# motordriver-v5_0_trinamic-controller.net
KiCad netlist of a schematic drawn in Altium Designer
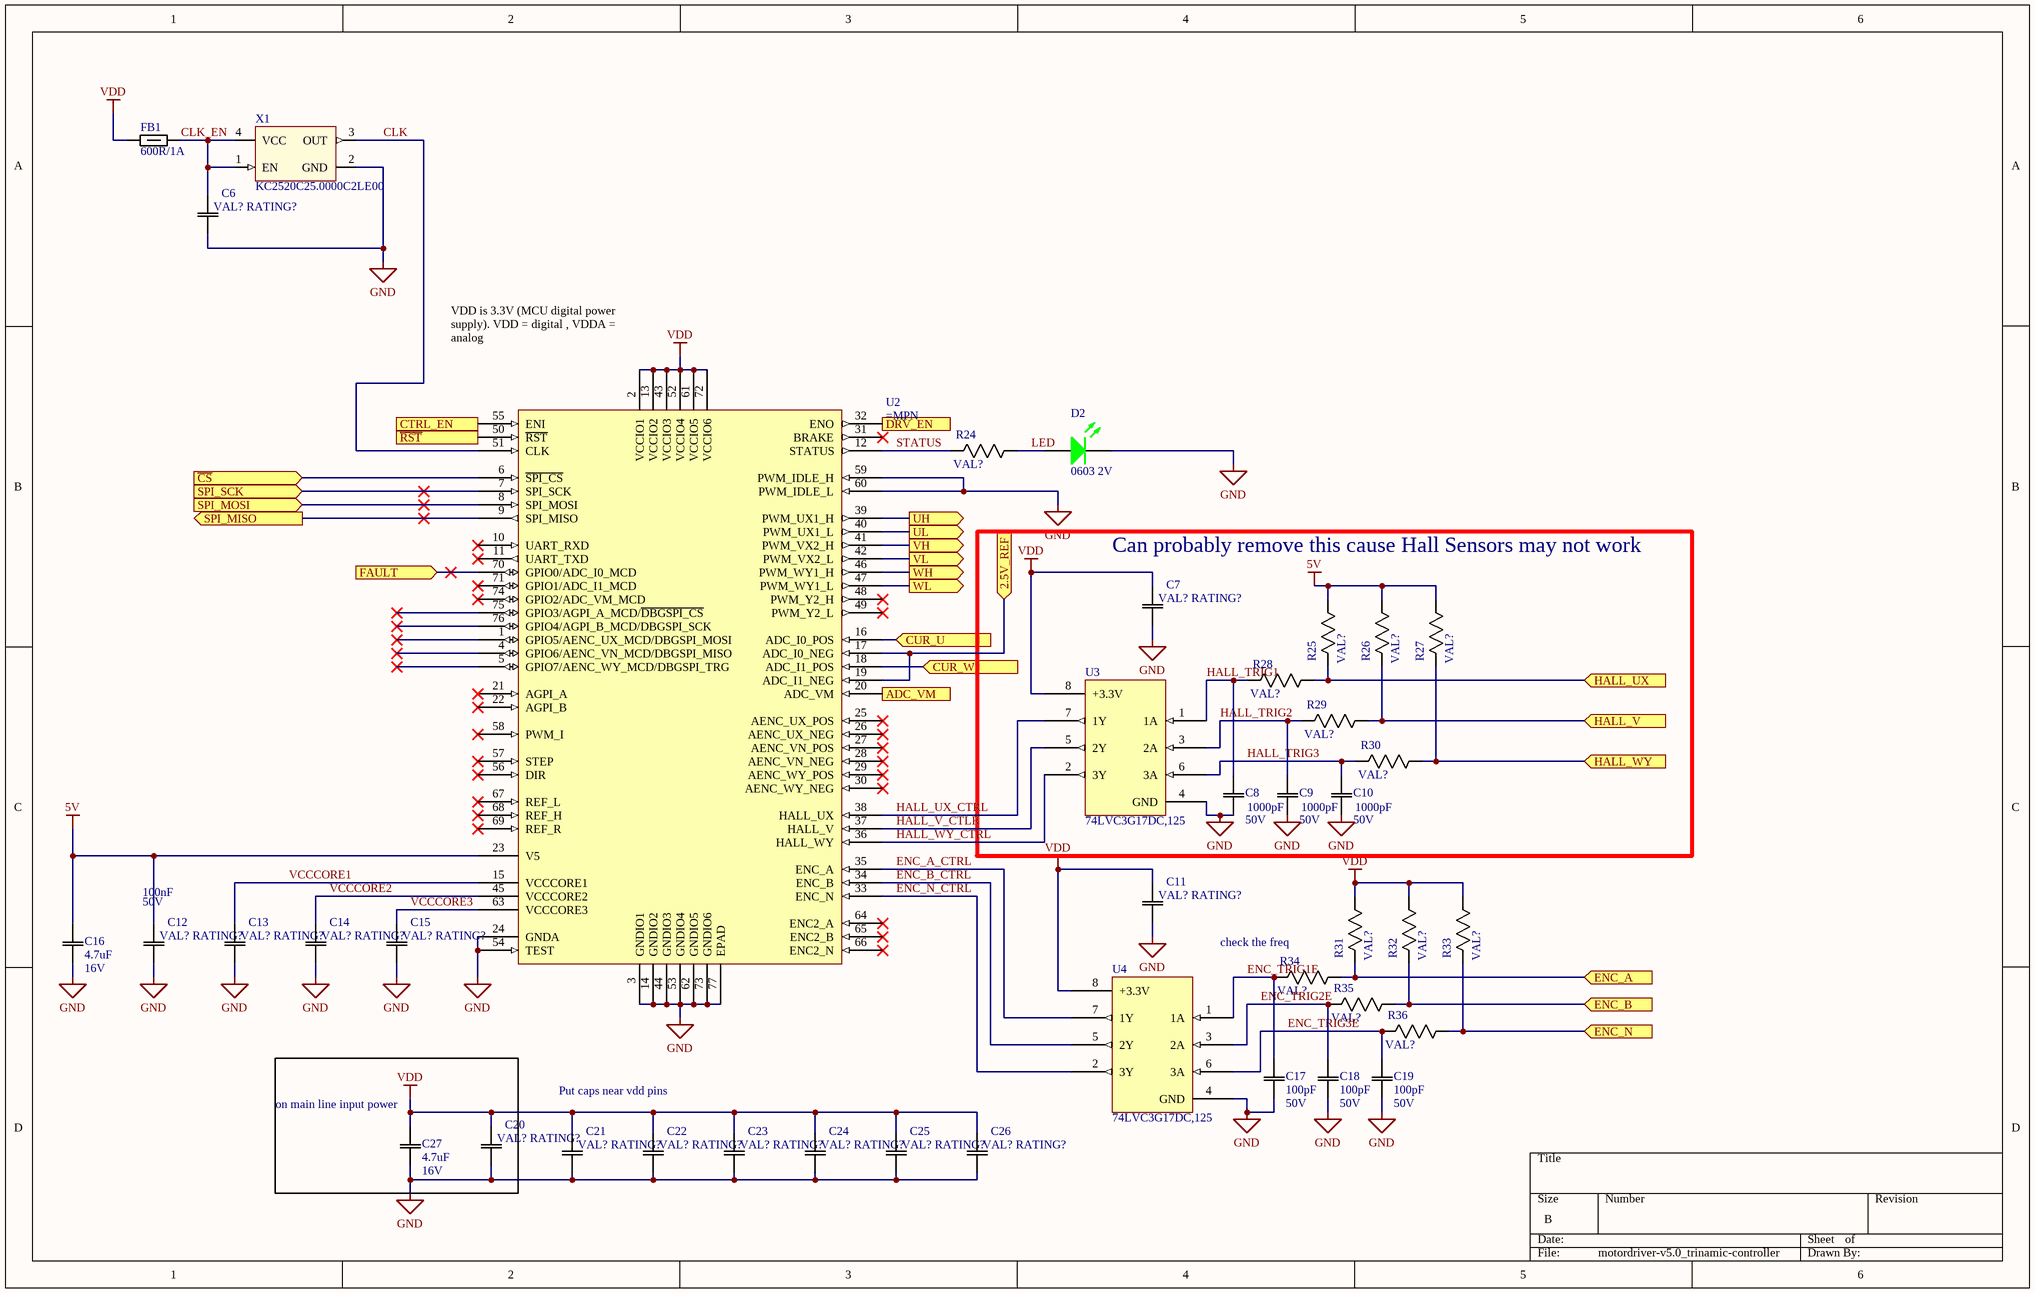
[diagram p0: motordriver-v5.0_trinamic-controller.SchDoc]

(export (version "E")
  (design (tool "Eeschema 10.0.6"))
  (components
    (comp (ref "C6")
      (value "VAL? RATING?")
      (footprint "0603")
      (description "Default Symbol for Capacitors")
      (fields (field (name "TOLERANCE") "10%") (field (name "PART NUMBER") "CAP 100nF 50V"))
      (libsource (lib "capacitor_library") (part "CAP_Default"))
    )
    (comp (ref "C7")
      (value "VAL? RATING?")
      (footprint "0603")
      (description "Default Symbol for Capacitors")
      (fields (field (name "TOLERANCE") "10%") (field (name "PART NUMBER") "CAP 100nF 50V"))
      (libsource (lib "capacitor_library") (part "CAP_Default"))
    )
    (comp (ref "C8")
      (value "1000pF")
      (footprint "0603")
      (description "Default Symbol for Capacitors")
      (fields
        (field (name "TOLERANCE") "10%")
        (field (name "RATING") "50V")
        (field (name "PART NUMBER") "CAP 1000pF 50V")
      )
      (libsource (lib "capacitor_library") (part "CAP_Default"))
    )
    (comp (ref "C9")
      (value "1000pF")
      (footprint "0603")
      (description "Default Symbol for Capacitors")
      (fields
        (field (name "TOLERANCE") "10%")
        (field (name "RATING") "50V")
        (field (name "PART NUMBER") "CAP 1000pF 50V")
      )
      (libsource (lib "capacitor_library") (part "CAP_Default"))
    )
    (comp (ref "C10")
      (value "1000pF")
      (footprint "0603")
      (description "Default Symbol for Capacitors")
      (fields
        (field (name "TOLERANCE") "10%")
        (field (name "RATING") "50V")
        (field (name "PART NUMBER") "CAP 1000pF 50V")
      )
      (libsource (lib "capacitor_library") (part "CAP_Default"))
    )
    (comp (ref "C11")
      (value "VAL? RATING?")
      (footprint "0603")
      (description "Default Symbol for Capacitors")
      (fields (field (name "TOLERANCE") "10%") (field (name "PART NUMBER") "CAP 100nF 50V"))
      (libsource (lib "capacitor_library") (part "CAP_Default"))
    )
    (comp (ref "C12")
      (value "VAL? RATING?")
      (footprint "0603")
      (description "Default Symbol for Capacitors")
      (fields
        (field (name "ALTIUM_VALUE") "100nF")
        (field (name "TOLERANCE") "10%")
        (field (name "RATING") "50V")
        (field (name "PART NUMBER") "CAP 100nF 50V")
      )
      (libsource (lib "capacitor_library") (part "CAP_Default"))
    )
    (comp (ref "C13")
      (value "VAL? RATING?")
      (footprint "0603")
      (description "Default Symbol for Capacitors")
      (fields (field (name "TOLERANCE") "10%") (field (name "PART NUMBER") "CAP 100nF 50V"))
      (libsource (lib "capacitor_library") (part "CAP_Default"))
    )
    (comp (ref "C14")
      (value "VAL? RATING?")
      (footprint "0603")
      (description "Default Symbol for Capacitors")
      (fields (field (name "TOLERANCE") "10%") (field (name "PART NUMBER") "CAP 100nF 50V"))
      (libsource (lib "capacitor_library") (part "CAP_Default"))
    )
    (comp (ref "C15")
      (value "VAL? RATING?")
      (footprint "0603")
      (description "Default Symbol for Capacitors")
      (fields (field (name "TOLERANCE") "10%") (field (name "PART NUMBER") "CAP 100nF 50V"))
      (libsource (lib "capacitor_library") (part "CAP_Default"))
    )
    (comp (ref "C16")
      (value "4.7uF")
      (footprint "0603")
      (description "Default Symbol for Capacitors")
      (fields
        (field (name "TOLERANCE") "10%")
        (field (name "RATING") "16V")
        (field (name "PART NUMBER") "CAP 4.7uF 16V")
      )
      (libsource (lib "capacitor_library") (part "CAP_Default"))
    )
    (comp (ref "C17")
      (value "100pF")
      (footprint "0603")
      (description "Default Symbol for Capacitors")
      (fields
        (field (name "TOLERANCE") "10%")
        (field (name "RATING") "50V")
        (field (name "PART NUMBER") "CAP 100pF 50V")
      )
      (libsource (lib "capacitor_library") (part "CAP_Default"))
    )
    (comp (ref "C18")
      (value "100pF")
      (footprint "0603")
      (description "Default Symbol for Capacitors")
      (fields
        (field (name "TOLERANCE") "10%")
        (field (name "RATING") "50V")
        (field (name "PART NUMBER") "CAP 100pF 50V")
      )
      (libsource (lib "capacitor_library") (part "CAP_Default"))
    )
    (comp (ref "C19")
      (value "100pF")
      (footprint "0603")
      (description "Default Symbol for Capacitors")
      (fields
        (field (name "TOLERANCE") "10%")
        (field (name "RATING") "50V")
        (field (name "PART NUMBER") "CAP 100pF 50V")
      )
      (libsource (lib "capacitor_library") (part "CAP_Default"))
    )
    (comp (ref "C20")
      (value "VAL? RATING?")
      (footprint "0603")
      (description "Default Symbol for Capacitors")
      (fields (field (name "TOLERANCE") "10%") (field (name "PART NUMBER") "CAP 470nF 50V"))
      (libsource (lib "capacitor_library") (part "CAP_Default"))
    )
    (comp (ref "C21")
      (value "VAL? RATING?")
      (footprint "0603")
      (description "Default Symbol for Capacitors")
      (fields (field (name "TOLERANCE") "10%") (field (name "PART NUMBER") "CAP 100nF 50V"))
      (libsource (lib "capacitor_library") (part "CAP_Default"))
    )
    (comp (ref "C22")
      (value "VAL? RATING?")
      (footprint "0603")
      (description "Default Symbol for Capacitors")
      (fields (field (name "TOLERANCE") "10%") (field (name "PART NUMBER") "CAP 100nF 50V"))
      (libsource (lib "capacitor_library") (part "CAP_Default"))
    )
    (comp (ref "C23")
      (value "VAL? RATING?")
      (footprint "0603")
      (description "Default Symbol for Capacitors")
      (fields (field (name "TOLERANCE") "10%") (field (name "PART NUMBER") "CAP 100nF 50V"))
      (libsource (lib "capacitor_library") (part "CAP_Default"))
    )
    (comp (ref "C24")
      (value "VAL? RATING?")
      (footprint "0603")
      (description "Default Symbol for Capacitors")
      (fields (field (name "TOLERANCE") "10%") (field (name "PART NUMBER") "CAP 100nF 50V"))
      (libsource (lib "capacitor_library") (part "CAP_Default"))
    )
    (comp (ref "C25")
      (value "VAL? RATING?")
      (footprint "0603")
      (description "Default Symbol for Capacitors")
      (fields (field (name "TOLERANCE") "10%") (field (name "PART NUMBER") "CAP 100nF 50V"))
      (libsource (lib "capacitor_library") (part "CAP_Default"))
    )
    (comp (ref "C26")
      (value "VAL? RATING?")
      (footprint "0603")
      (description "Default Symbol for Capacitors")
      (fields (field (name "TOLERANCE") "10%") (field (name "PART NUMBER") "CAP 100nF 50V"))
      (libsource (lib "capacitor_library") (part "CAP_Default"))
    )
    (comp (ref "C27")
      (value "4.7uF")
      (footprint "0603")
      (description "Default Symbol for Capacitors")
      (fields
        (field (name "TOLERANCE") "10%")
        (field (name "RATING") "16V")
        (field (name "PART NUMBER") "CAP 4.7uF 16V")
      )
      (libsource (lib "capacitor_library") (part "CAP_Default"))
    )
    (comp (ref "D2")
      (value "0603 2V")
      (footprint "0603 - LED")
      (description "LED Uni-Color Green 574nm 2-Pin Chip LED T/R")
      (fields
        (field (name "MANUFACTURER PART NUMBER") "LTST-C190KGKT")
        (field (name "PART NUMBER") "LED GREEN SMD 0603")
      )
      (libsource (lib "Diode_Library") (part "LED GREEN SMD 0603"))
    )
    (comp (ref "FB1")
      (value "600R/1A")
      (footprint "0603")
      (fields
        (field (name "MANUFACTURER PART NUMBER") "742792651-220-R")
        (field (name "PART NUMBER") "FERRITE BEAD 200 MOHM 0603 1LN")
      )
      (libsource (lib "Inductor_Library") (part "FERRITE BEAD 200 MOHM 0603 1LN"))
    )
    (comp (ref "R24")
      (value "VAL?")
      (footprint "0603")
      (description "Default Resistor Symbol")
      (fields (field (name "TOLERANCE") "5%") (field (name "PART NUMBER") "RES 75.0 1/8W - 5%"))
      (libsource (lib "Resistor_Library") (part "RES_DEFAULT"))
    )
    (comp (ref "R25")
      (value "VAL?")
      (footprint "0603")
      (description "Default Resistor Symbol")
      (fields (field (name "TOLERANCE") "5%") (field (name "PART NUMBER") "RES 4.7k 1/8W - 5%"))
      (libsource (lib "Resistor_Library") (part "RES_DEFAULT"))
    )
    (comp (ref "R26")
      (value "VAL?")
      (footprint "0603")
      (description "Default Resistor Symbol")
      (fields (field (name "TOLERANCE") "5%") (field (name "PART NUMBER") "RES 4.7k 1/8W - 5%"))
      (libsource (lib "Resistor_Library") (part "RES_DEFAULT"))
    )
    (comp (ref "R27")
      (value "VAL?")
      (footprint "0603")
      (description "Default Resistor Symbol")
      (fields (field (name "TOLERANCE") "5%") (field (name "PART NUMBER") "RES 4.7k 1/8W - 5%"))
      (libsource (lib "") (part "RES_DEFAULT_1"))
    )
    (comp (ref "R28")
      (value "VAL?")
      (footprint "0603")
      (description "Default Resistor Symbol")
      (fields (field (name "TOLERANCE") "5%") (field (name "PART NUMBER") "RES 4.7k 1/8W - 5%"))
      (libsource (lib "Resistor_Library") (part "RES_DEFAULT"))
    )
    (comp (ref "R29")
      (value "VAL?")
      (footprint "0603")
      (description "Default Resistor Symbol")
      (fields (field (name "TOLERANCE") "5%") (field (name "PART NUMBER") "RES 4.7k 1/8W - 5%"))
      (libsource (lib "Resistor_Library") (part "RES_DEFAULT"))
    )
    (comp (ref "R30")
      (value "VAL?")
      (footprint "0603")
      (description "Default Resistor Symbol")
      (fields (field (name "TOLERANCE") "5%") (field (name "PART NUMBER") "RES 4.7k 1/8W - 5%"))
      (libsource (lib "Resistor_Library") (part "RES_DEFAULT"))
    )
    (comp (ref "R31")
      (value "VAL?")
      (footprint "0603")
      (description "Default Resistor Symbol")
      (fields (field (name "TOLERANCE") "5%") (field (name "PART NUMBER") "RES 4.7k 1/8W - 5%"))
      (libsource (lib "Resistor_Library") (part "RES_DEFAULT"))
    )
    (comp (ref "R32")
      (value "VAL?")
      (footprint "0603")
      (description "Default Resistor Symbol")
      (fields (field (name "TOLERANCE") "5%") (field (name "PART NUMBER") "RES 4.7k 1/8W - 5%"))
      (libsource (lib "Resistor_Library") (part "RES_DEFAULT"))
    )
    (comp (ref "R33")
      (value "VAL?")
      (footprint "0603")
      (description "Default Resistor Symbol")
      (fields (field (name "TOLERANCE") "5%") (field (name "PART NUMBER") "RES 4.7k 1/8W - 5%"))
      (libsource (lib "") (part "RES_DEFAULT_1"))
    )
    (comp (ref "R34")
      (value "VAL?")
      (footprint "0603")
      (description "Default Resistor Symbol")
      (fields (field (name "TOLERANCE") "1%") (field (name "PART NUMBER") "RES 1k 1/8W - 1%"))
      (libsource (lib "") (part "RES_DEFAULT_1"))
    )
    (comp (ref "R35")
      (value "VAL?")
      (footprint "0603")
      (description "Default Resistor Symbol")
      (fields (field (name "TOLERANCE") "1%") (field (name "PART NUMBER") "RES 1k 1/8W - 1%"))
      (libsource (lib "Resistor_Library") (part "RES_DEFAULT"))
    )
    (comp (ref "R36")
      (value "VAL?")
      (footprint "0603")
      (description "Default Resistor Symbol")
      (fields (field (name "TOLERANCE") "1%") (field (name "PART NUMBER") "RES 1k 1/8W - 1%"))
      (libsource (lib "") (part "RES_DEFAULT_1"))
    )
    (comp (ref "U2")
      (value "~")
      (footprint "QFN40P1050X650X90_HS-77N")
      (description "Motor Driver, -40 To 125Deg C Rohs Compliant: Yes")
      (fields (field (name "MANUFACTURER PART NUMBER") "TMC4671-LA") (field (name "PART NUMBER") "TMC4671"))
      (libsource (lib "IC_Library") (part "TMC4671"))
    )
    (comp (ref "U3")
      (value "74LVC3G17DC,125")
      (footprint "8-VSSOP")
      (description "IC BUFFER TRIPLE SCHMITT TRIGGER 5.5V VSSOP-8")
      (fields (field (name "MANUFACTURER") "Nexperia"))
      (libsource (lib "AltiumLibraries") (part "IC 74LVC3G17DC,125"))
    )
    (comp (ref "U4")
      (value "74LVC3G17DC,125")
      (footprint "8-VSSOP")
      (description "IC BUFFER TRIPLE SCHMITT TRIGGER 5.5V VSSOP-8")
      (fields (field (name "MANUFACTURER") "Nexperia"))
      (libsource (lib "AltiumLibraries") (part "IC 74LVC3G17DC,125"))
    )
    (comp (ref "X1")
      (value "KC2520C25.0000C2LE00")
      (footprint "KC2520C25.0000C2LE00")
      (description "Oscillator XO 25MHz ±15ppm 15pF CMOS 55% 2.5V/3.3V 4-Pin Mini-CSMD T/R")
      (fields (field (name "PART NUMBER") "XTAL OSC 25MHz 3.3V"))
      (libsource (lib "Oscillator_Library") (part "XTAL OSC 25MHz 3.3V"))
    )
  )
  (nets
    (net (code "1") (name "/2.5V_REF") (class "Default")
      (node (ref "U2") (pin "17") (pinfunction "ADC_I0_NEG_17") (pintype "input"))
      (node (ref "U2") (pin "19") (pinfunction "ADC_I1_NEG_19") (pintype "input"))
    )
    (net (code "2") (name "/ADC_VM") (class "Default")
      (node (ref "U2") (pin "20") (pinfunction "ADC_VM_20") (pintype "input"))
    )
    (net (code "3") (name "/CLK") (class "Default")
      (node (ref "U2") (pin "51") (pinfunction "CLK_51") (pintype "input"))
      (node (ref "X1") (pin "3") (pinfunction "OUT_3") (pintype "output"))
    )
    (net (code "4") (name "/CLK_EN") (class "Default")
      (node (ref "C6") (pin "2") (pinfunction "C2_2") (pintype "passive"))
      (node (ref "FB1") (pin "2") (pinfunction "2_2") (pintype "passive"))
      (node (ref "X1") (pin "1") (pinfunction "EN_1") (pintype "input"))
      (node (ref "X1") (pin "4") (pinfunction "VCC_4") (pintype "power_in"))
    )
    (net (code "5") (name "/CTRL_EN") (class "Default")
      (node (ref "U2") (pin "55") (pinfunction "ENI_55") (pintype "input"))
    )
    (net (code "6") (name "/CUR_U") (class "Default")
      (node (ref "U2") (pin "16") (pinfunction "ADC_I0_POS_16") (pintype "input"))
    )
    (net (code "7") (name "/CUR_W") (class "Default")
      (node (ref "U2") (pin "18") (pinfunction "ADC_I1_POS_18") (pintype "input"))
    )
    (net (code "8") (name "/DRV_EN") (class "Default")
      (node (ref "U2") (pin "32") (pinfunction "ENO_32") (pintype "output"))
    )
    (net (code "9") (name "/ENC_A") (class "Default")
      (node (ref "R31") (pin "2") (pinfunction "R2_2") (pintype "passive"))
      (node (ref "R34") (pin "1") (pinfunction "R1_1") (pintype "passive"))
    )
    (net (code "10") (name "/ENC_A_CTRL") (class "Default")
      (node (ref "U2") (pin "35") (pinfunction "ENC_A_35") (pintype "input"))
      (node (ref "U4") (pin "7") (pinfunction "1Y_7") (pintype "output"))
    )
    (net (code "11") (name "/ENC_B") (class "Default")
      (node (ref "R32") (pin "2") (pinfunction "R2_2") (pintype "passive"))
      (node (ref "R35") (pin "1") (pinfunction "R1_1") (pintype "passive"))
    )
    (net (code "12") (name "/ENC_B_CTRL") (class "Default")
      (node (ref "U2") (pin "34") (pinfunction "ENC_B_34") (pintype "input"))
      (node (ref "U4") (pin "5") (pinfunction "2Y_5") (pintype "output"))
    )
    (net (code "13") (name "/ENC_N") (class "Default")
      (node (ref "R33") (pin "2") (pinfunction "R2_2") (pintype "passive"))
      (node (ref "R36") (pin "1") (pinfunction "R1_1") (pintype "passive"))
    )
    (net (code "14") (name "/ENC_N_CTRL") (class "Default")
      (node (ref "U2") (pin "33") (pinfunction "ENC_N_33") (pintype "input"))
      (node (ref "U4") (pin "2") (pinfunction "3Y_2") (pintype "output"))
    )
    (net (code "15") (name "/ENC_TRIG1E") (class "Default")
      (node (ref "C17") (pin "2") (pinfunction "C2_2") (pintype "passive"))
      (node (ref "R34") (pin "2") (pinfunction "R2_2") (pintype "passive"))
      (node (ref "U4") (pin "1") (pinfunction "1A_1") (pintype "input"))
    )
    (net (code "16") (name "/ENC_TRIG2E") (class "Default")
      (node (ref "C18") (pin "2") (pinfunction "C2_2") (pintype "passive"))
      (node (ref "R35") (pin "2") (pinfunction "R2_2") (pintype "passive"))
      (node (ref "U4") (pin "3") (pinfunction "2A_3") (pintype "input"))
    )
    (net (code "17") (name "/ENC_TRIG3E") (class "Default")
      (node (ref "C19") (pin "2") (pinfunction "C2_2") (pintype "passive"))
      (node (ref "R36") (pin "2") (pinfunction "R2_2") (pintype "passive"))
      (node (ref "U4") (pin "6") (pinfunction "3A_6") (pintype "input"))
    )
    (net (code "18") (name "/FAULT") (class "Default")
      (node (ref "U2") (pin "70") (pinfunction "GPIO0/ADC_I0_MCD_70") (pintype "bidirectional"))
    )
    (net (code "19") (name "/HALL_TRIG1") (class "Default")
      (node (ref "C8") (pin "2") (pinfunction "C2_2") (pintype "passive"))
      (node (ref "R28") (pin "2") (pinfunction "R2_2") (pintype "passive"))
      (node (ref "U3") (pin "1") (pinfunction "1A_1") (pintype "input"))
    )
    (net (code "20") (name "/HALL_TRIG2") (class "Default")
      (node (ref "C9") (pin "2") (pinfunction "C2_2") (pintype "passive"))
      (node (ref "R29") (pin "2") (pinfunction "R2_2") (pintype "passive"))
      (node (ref "U3") (pin "3") (pinfunction "2A_3") (pintype "input"))
    )
    (net (code "21") (name "/HALL_TRIG3") (class "Default")
      (node (ref "C10") (pin "2") (pinfunction "C2_2") (pintype "passive"))
      (node (ref "R30") (pin "2") (pinfunction "R2_2") (pintype "passive"))
      (node (ref "U3") (pin "6") (pinfunction "3A_6") (pintype "input"))
    )
    (net (code "22") (name "/HALL_UX") (class "Default")
      (node (ref "R25") (pin "2") (pinfunction "R2_2") (pintype "passive"))
      (node (ref "R28") (pin "1") (pinfunction "R1_1") (pintype "passive"))
    )
    (net (code "23") (name "/HALL_UX_CTRL") (class "Default")
      (node (ref "U2") (pin "38") (pinfunction "HALL_UX_38") (pintype "input"))
      (node (ref "U3") (pin "7") (pinfunction "1Y_7") (pintype "output"))
    )
    (net (code "24") (name "/HALL_V") (class "Default")
      (node (ref "R26") (pin "2") (pinfunction "R2_2") (pintype "passive"))
      (node (ref "R29") (pin "1") (pinfunction "R1_1") (pintype "passive"))
    )
    (net (code "25") (name "/HALL_V_CTLR") (class "Default")
      (node (ref "U2") (pin "37") (pinfunction "HALL_V_37") (pintype "input"))
      (node (ref "U3") (pin "5") (pinfunction "2Y_5") (pintype "output"))
    )
    (net (code "26") (name "/HALL_WY") (class "Default")
      (node (ref "R27") (pin "2") (pinfunction "R2_2") (pintype "passive"))
      (node (ref "R30") (pin "1") (pinfunction "R1_1") (pintype "passive"))
    )
    (net (code "27") (name "/HALL_WY_CTRL") (class "Default")
      (node (ref "U2") (pin "36") (pinfunction "HALL_WY_36") (pintype "input"))
      (node (ref "U3") (pin "2") (pinfunction "3Y_2") (pintype "output"))
    )
    (net (code "28") (name "/LED") (class "Default")
      (node (ref "D2") (pin "1") (pinfunction "A_1") (pintype "passive"))
      (node (ref "R24") (pin "1") (pinfunction "R1_1") (pintype "passive"))
    )
    (net (code "29") (name "/SPI_MISO") (class "Default")
      (node (ref "U2") (pin "9") (pinfunction "SPI_MISO_9") (pintype "output"))
    )
    (net (code "30") (name "/SPI_MOSI") (class "Default")
      (node (ref "U2") (pin "8") (pinfunction "SPI_MOSI_8") (pintype "input"))
    )
    (net (code "31") (name "/SPI_SCK") (class "Default")
      (node (ref "U2") (pin "7") (pinfunction "SPI_SCK_7") (pintype "input"))
    )
    (net (code "32") (name "/STATUS") (class "Default")
      (node (ref "R24") (pin "2") (pinfunction "R2_2") (pintype "passive"))
      (node (ref "U2") (pin "12") (pinfunction "STATUS_12") (pintype "output"))
    )
    (net (code "33") (name "/UH") (class "Default")
      (node (ref "U2") (pin "39") (pinfunction "PWM_UX1_H_39") (pintype "output"))
    )
    (net (code "34") (name "/UL") (class "Default")
      (node (ref "U2") (pin "40") (pinfunction "PWM_UX1_L_40") (pintype "output"))
    )
    (net (code "35") (name "/VCCCORE1") (class "Default")
      (node (ref "C13") (pin "2") (pinfunction "C2_2") (pintype "passive"))
      (node (ref "U2") (pin "15") (pinfunction "VCCCORE1_15") (pintype "power_in"))
    )
    (net (code "36") (name "/VCCCORE2") (class "Default")
      (node (ref "C14") (pin "2") (pinfunction "C2_2") (pintype "passive"))
      (node (ref "U2") (pin "45") (pinfunction "VCCCORE2_45") (pintype "power_in"))
    )
    (net (code "37") (name "/VCCCORE3") (class "Default")
      (node (ref "C15") (pin "2") (pinfunction "C2_2") (pintype "passive"))
      (node (ref "U2") (pin "63") (pinfunction "VCCCORE3_63") (pintype "power_in"))
    )
    (net (code "38") (name "/VH") (class "Default")
      (node (ref "U2") (pin "41") (pinfunction "PWM_VX2_H_41") (pintype "output"))
    )
    (net (code "39") (name "/VL") (class "Default")
      (node (ref "U2") (pin "42") (pinfunction "PWM_VX2_L_42") (pintype "output"))
    )
    (net (code "40") (name "/WH") (class "Default")
      (node (ref "U2") (pin "46") (pinfunction "PWM_WY1_H_46") (pintype "output"))
    )
    (net (code "41") (name "/WL") (class "Default")
      (node (ref "U2") (pin "47") (pinfunction "PWM_WY1_L_47") (pintype "output"))
    )
    (net (code "42") (name "/~{CS}") (class "Default")
      (node (ref "U2") (pin "6") (pinfunction "~{SPI_CS}_6") (pintype "input"))
    )
    (net (code "43") (name "/~{RST}") (class "Default")
      (node (ref "U2") (pin "50") (pinfunction "~{RST}_50") (pintype "input"))
    )
    (net (code "44") (name "5V") (class "Default")
      (node (ref "C12") (pin "2") (pinfunction "C2_2") (pintype "passive"))
      (node (ref "C16") (pin "2") (pinfunction "C2_2") (pintype "passive"))
      (node (ref "R25") (pin "1") (pinfunction "R1_1") (pintype "passive"))
      (node (ref "R26") (pin "1") (pinfunction "R1_1") (pintype "passive"))
      (node (ref "R27") (pin "1") (pinfunction "R1_1") (pintype "passive"))
      (node (ref "U2") (pin "23") (pinfunction "V5_23") (pintype "power_in"))
    )
    (net (code "45") (name "GND") (class "Default")
      (node (ref "C10") (pin "1") (pinfunction "C1_1") (pintype "passive"))
      (node (ref "C11") (pin "1") (pinfunction "C1_1") (pintype "passive"))
      (node (ref "C12") (pin "1") (pinfunction "C1_1") (pintype "passive"))
      (node (ref "C13") (pin "1") (pinfunction "C1_1") (pintype "passive"))
      (node (ref "C14") (pin "1") (pinfunction "C1_1") (pintype "passive"))
      (node (ref "C15") (pin "1") (pinfunction "C1_1") (pintype "passive"))
      (node (ref "C16") (pin "1") (pinfunction "C1_1") (pintype "passive"))
      (node (ref "C17") (pin "1") (pinfunction "C1_1") (pintype "passive"))
      (node (ref "C18") (pin "1") (pinfunction "C1_1") (pintype "passive"))
      (node (ref "C19") (pin "1") (pinfunction "C1_1") (pintype "passive"))
      (node (ref "C20") (pin "1") (pinfunction "C1_1") (pintype "passive"))
      (node (ref "C21") (pin "1") (pinfunction "C1_1") (pintype "passive"))
      (node (ref "C22") (pin "1") (pinfunction "C1_1") (pintype "passive"))
      (node (ref "C23") (pin "1") (pinfunction "C1_1") (pintype "passive"))
      (node (ref "C24") (pin "1") (pinfunction "C1_1") (pintype "passive"))
      (node (ref "C25") (pin "1") (pinfunction "C1_1") (pintype "passive"))
      (node (ref "C26") (pin "1") (pinfunction "C1_1") (pintype "passive"))
      (node (ref "C27") (pin "1") (pinfunction "C1_1") (pintype "passive"))
      (node (ref "C6") (pin "1") (pinfunction "C1_1") (pintype "passive"))
      (node (ref "C7") (pin "1") (pinfunction "C1_1") (pintype "passive"))
      (node (ref "C8") (pin "1") (pinfunction "C1_1") (pintype "passive"))
      (node (ref "C9") (pin "1") (pinfunction "C1_1") (pintype "passive"))
      (node (ref "D2") (pin "2") (pinfunction "K_2") (pintype "passive"))
      (node (ref "U2") (pin "14") (pinfunction "GNDIO2_14") (pintype "power_in"))
      (node (ref "U2") (pin "24") (pinfunction "GNDA_24") (pintype "power_in"))
      (node (ref "U2") (pin "3") (pinfunction "GNDIO1_3") (pintype "power_in"))
      (node (ref "U2") (pin "44") (pinfunction "GNDIO3_44") (pintype "power_in"))
      (node (ref "U2") (pin "53") (pinfunction "GNDIO4_53") (pintype "power_in"))
      (node (ref "U2") (pin "54") (pinfunction "TEST_54") (pintype "input"))
      (node (ref "U2") (pin "59") (pinfunction "PWM_IDLE_H_59") (pintype "input"))
      (node (ref "U2") (pin "60") (pinfunction "PWM_IDLE_L_60") (pintype "input"))
      (node (ref "U2") (pin "62") (pinfunction "GNDIO5_62") (pintype "power_in"))
      (node (ref "U2") (pin "73") (pinfunction "GNDIO6_73") (pintype "power_in"))
      (node (ref "U2") (pin "77") (pinfunction "EPAD_77") (pintype "passive"))
      (node (ref "U3") (pin "4") (pinfunction "GND_4") (pintype "power_in"))
      (node (ref "U4") (pin "4") (pinfunction "GND_4") (pintype "power_in"))
      (node (ref "X1") (pin "2") (pinfunction "GND_2") (pintype "power_in"))
    )
    (net (code "46") (name "VDD") (class "Default")
      (node (ref "C11") (pin "2") (pinfunction "C2_2") (pintype "passive"))
      (node (ref "C20") (pin "2") (pinfunction "C2_2") (pintype "passive"))
      (node (ref "C21") (pin "2") (pinfunction "C2_2") (pintype "passive"))
      (node (ref "C22") (pin "2") (pinfunction "C2_2") (pintype "passive"))
      (node (ref "C23") (pin "2") (pinfunction "C2_2") (pintype "passive"))
      (node (ref "C24") (pin "2") (pinfunction "C2_2") (pintype "passive"))
      (node (ref "C25") (pin "2") (pinfunction "C2_2") (pintype "passive"))
      (node (ref "C26") (pin "2") (pinfunction "C2_2") (pintype "passive"))
      (node (ref "C27") (pin "2") (pinfunction "C2_2") (pintype "passive"))
      (node (ref "C7") (pin "2") (pinfunction "C2_2") (pintype "passive"))
      (node (ref "FB1") (pin "1") (pinfunction "1_1") (pintype "passive"))
      (node (ref "R31") (pin "1") (pinfunction "R1_1") (pintype "passive"))
      (node (ref "R32") (pin "1") (pinfunction "R1_1") (pintype "passive"))
      (node (ref "R33") (pin "1") (pinfunction "R1_1") (pintype "passive"))
      (node (ref "U2") (pin "13") (pinfunction "VCCIO2_13") (pintype "power_in"))
      (node (ref "U2") (pin "2") (pinfunction "VCCIO1_2") (pintype "power_in"))
      (node (ref "U2") (pin "43") (pinfunction "VCCIO3_43") (pintype "power_in"))
      (node (ref "U2") (pin "52") (pinfunction "VCCIO4_52") (pintype "power_in"))
      (node (ref "U2") (pin "61") (pinfunction "VCCIO5_61") (pintype "power_in"))
      (node (ref "U2") (pin "72") (pinfunction "VCCIO6_72") (pintype "power_in"))
      (node (ref "U3") (pin "8") (pinfunction "+3.3V_8") (pintype "power_in"))
      (node (ref "U4") (pin "8") (pinfunction "+3.3V_8") (pintype "power_in"))
    )
    (net (code "47") (name "unconnected-(U2-AENC_UX_NEG-Pad26)") (class "Default")
      (node (ref "U2") (pin "26") (pinfunction "AENC_UX_NEG_26") (pintype "input+no_connect"))
    )
    (net (code "48") (name "unconnected-(U2-AENC_UX_POS-Pad25)") (class "Default")
      (node (ref "U2") (pin "25") (pinfunction "AENC_UX_POS_25") (pintype "input+no_connect"))
    )
    (net (code "49") (name "unconnected-(U2-AENC_VN_NEG-Pad28)") (class "Default")
      (node (ref "U2") (pin "28") (pinfunction "AENC_VN_NEG_28") (pintype "input+no_connect"))
    )
    (net (code "50") (name "unconnected-(U2-AENC_VN_POS-Pad27)") (class "Default")
      (node (ref "U2") (pin "27") (pinfunction "AENC_VN_POS_27") (pintype "input+no_connect"))
    )
    (net (code "51") (name "unconnected-(U2-AENC_WY_NEG-Pad30)") (class "Default")
      (node (ref "U2") (pin "30") (pinfunction "AENC_WY_NEG_30") (pintype "input+no_connect"))
    )
    (net (code "52") (name "unconnected-(U2-AENC_WY_POS-Pad29)") (class "Default")
      (node (ref "U2") (pin "29") (pinfunction "AENC_WY_POS_29") (pintype "input+no_connect"))
    )
    (net (code "53") (name "unconnected-(U2-AGPI_A-Pad21)") (class "Default")
      (node (ref "U2") (pin "21") (pinfunction "AGPI_A_21") (pintype "input+no_connect"))
    )
    (net (code "54") (name "unconnected-(U2-AGPI_B-Pad22)") (class "Default")
      (node (ref "U2") (pin "22") (pinfunction "AGPI_B_22") (pintype "input+no_connect"))
    )
    (net (code "55") (name "unconnected-(U2-BRAKE-Pad31)") (class "Default")
      (node (ref "U2") (pin "31") (pinfunction "BRAKE_31") (pintype "output+no_connect"))
    )
    (net (code "56") (name "unconnected-(U2-DIR-Pad56)") (class "Default")
      (node (ref "U2") (pin "56") (pinfunction "DIR_56") (pintype "input+no_connect"))
    )
    (net (code "57") (name "unconnected-(U2-ENC2_A-Pad64)") (class "Default")
      (node (ref "U2") (pin "64") (pinfunction "ENC2_A_64") (pintype "input+no_connect"))
    )
    (net (code "58") (name "unconnected-(U2-ENC2_B-Pad65)") (class "Default")
      (node (ref "U2") (pin "65") (pinfunction "ENC2_B_65") (pintype "input+no_connect"))
    )
    (net (code "59") (name "unconnected-(U2-ENC2_N-Pad66)") (class "Default")
      (node (ref "U2") (pin "66") (pinfunction "ENC2_N_66") (pintype "input+no_connect"))
    )
    (net (code "60") (name "unconnected-(U2-GPIO1{slash}ADC_I1_MCD-Pad71)") (class "Default")
      (node (ref "U2") (pin "71") (pinfunction "GPIO1/ADC_I1_MCD_71") (pintype "bidirectional+no_connect"))
    )
    (net (code "61") (name "unconnected-(U2-GPIO2{slash}ADC_VM_MCD-Pad74)") (class "Default")
      (node (ref "U2") (pin "74") (pinfunction "GPIO2/ADC_VM_MCD_74") (pintype "bidirectional+no_connect"))
    )
    (net (code "62") (name "unconnected-(U2-GPIO3{slash}AGPI_A_MCD{slash}~{DBGSPI_CS}-Pad75)") (class "Default")
      (node (ref "U2") (pin "75") (pinfunction "GPIO3/AGPI_A_MCD/~{DBGSPI_CS}_75") (pintype "bidirectional+no_connect"))
    )
    (net (code "63") (name "unconnected-(U2-GPIO4{slash}AGPI_B_MCD{slash}DBGSPI_SCK-Pad76)") (class "Default")
      (node (ref "U2") (pin "76") (pinfunction "GPIO4/AGPI_B_MCD/DBGSPI_SCK_76") (pintype "bidirectional+no_connect"))
    )
    (net (code "64") (name "unconnected-(U2-GPIO5{slash}AENC_UX_MCD{slash}DBGSPI_MOSI-Pad1)") (class "Default")
      (node (ref "U2") (pin "1") (pinfunction "GPIO5/AENC_UX_MCD/DBGSPI_MOSI_1") (pintype "bidirectional+no_connect"))
    )
    (net (code "65") (name "unconnected-(U2-GPIO6{slash}AENC_VN_MCD{slash}DBGSPI_MISO-Pad4)") (class "Default")
      (node (ref "U2") (pin "4") (pinfunction "GPIO6/AENC_VN_MCD/DBGSPI_MISO_4") (pintype "bidirectional+no_connect"))
    )
    (net (code "66") (name "unconnected-(U2-GPIO7{slash}AENC_WY_MCD{slash}DBGSPI_TRG-Pad5)") (class "Default")
      (node (ref "U2") (pin "5") (pinfunction "GPIO7/AENC_WY_MCD/DBGSPI_TRG_5") (pintype "bidirectional+no_connect"))
    )
    (net (code "67") (name "unconnected-(U2-PWM_I-Pad58)") (class "Default")
      (node (ref "U2") (pin "58") (pinfunction "PWM_I_58") (pintype "input+no_connect"))
    )
    (net (code "68") (name "unconnected-(U2-PWM_Y2_H-Pad48)") (class "Default")
      (node (ref "U2") (pin "48") (pinfunction "PWM_Y2_H_48") (pintype "output+no_connect"))
    )
    (net (code "69") (name "unconnected-(U2-PWM_Y2_L-Pad49)") (class "Default")
      (node (ref "U2") (pin "49") (pinfunction "PWM_Y2_L_49") (pintype "output+no_connect"))
    )
    (net (code "70") (name "unconnected-(U2-REF_H-Pad68)") (class "Default")
      (node (ref "U2") (pin "68") (pinfunction "REF_H_68") (pintype "input+no_connect"))
    )
    (net (code "71") (name "unconnected-(U2-REF_L-Pad67)") (class "Default")
      (node (ref "U2") (pin "67") (pinfunction "REF_L_67") (pintype "input+no_connect"))
    )
    (net (code "72") (name "unconnected-(U2-REF_R-Pad69)") (class "Default")
      (node (ref "U2") (pin "69") (pinfunction "REF_R_69") (pintype "input+no_connect"))
    )
    (net (code "73") (name "unconnected-(U2-STEP-Pad57)") (class "Default")
      (node (ref "U2") (pin "57") (pinfunction "STEP_57") (pintype "input+no_connect"))
    )
    (net (code "74") (name "unconnected-(U2-UART_RXD-Pad10)") (class "Default")
      (node (ref "U2") (pin "10") (pinfunction "UART_RXD_10") (pintype "input+no_connect"))
    )
    (net (code "75") (name "unconnected-(U2-UART_TXD-Pad11)") (class "Default")
      (node (ref "U2") (pin "11") (pinfunction "UART_TXD_11") (pintype "output+no_connect"))
    )
  )
)
